# Soundtrap_IMU_board_v4_RXTX_switch.net
KiCad netlist of a schematic drawn in EAGLE
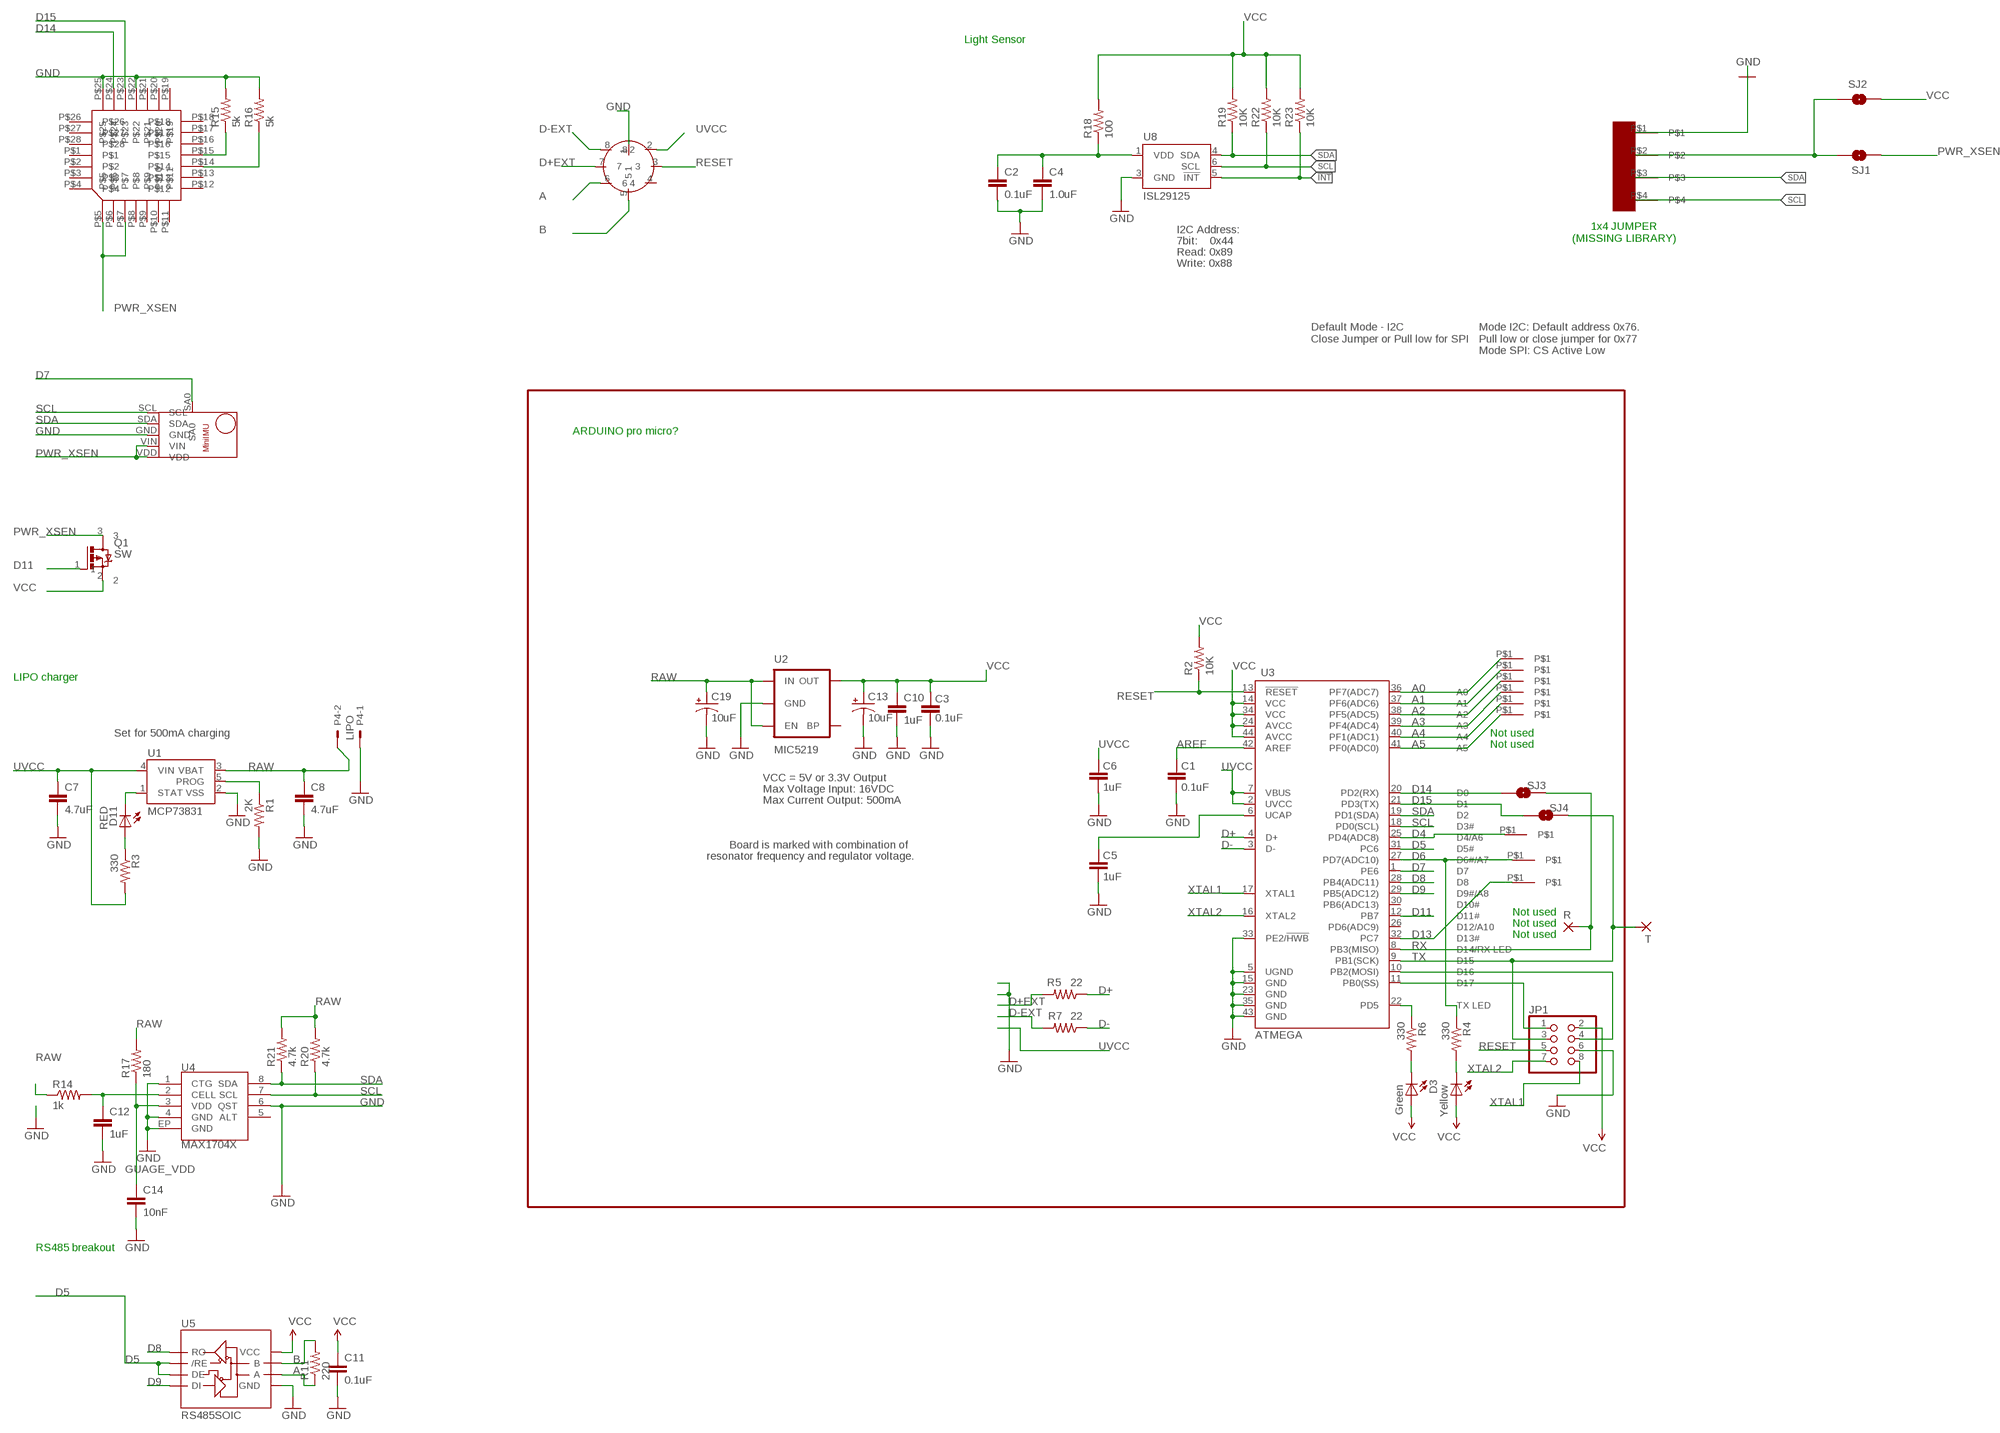
[diagram p0: schematic, sheet 1]

(export (version "E")
  (design (tool "Eeschema 10.0.6"))
  (components
    (comp (ref "C1")
      (value "0.1uF")
      (footprint "eagle-import:0603-CAP")
      (libsource (lib "eagle-import") (part "CAP0603-CAP"))
    )
    (comp (ref "C2")
      (value "0.1uF")
      (footprint "eagle-import:0603-CAP")
      (libsource (lib "eagle-import") (part "0.1UF-25V(+80/-20%)(0603)"))
    )
    (comp (ref "C3")
      (value "0.1uF")
      (footprint "eagle-import:0603-CAP")
      (libsource (lib "eagle-import") (part "CAP0603-CAP"))
    )
    (comp (ref "C4")
      (value "1.0uF")
      (footprint "eagle-import:0603-CAP")
      (libsource (lib "eagle-import") (part "1.0UF-16V-10%(0603)"))
    )
    (comp (ref "C5")
      (value "1uF")
      (footprint "eagle-import:0603-CAP")
      (libsource (lib "eagle-import") (part "CAP0603-CAP"))
    )
    (comp (ref "C6")
      (value "1uF")
      (footprint "eagle-import:0603-CAP")
      (libsource (lib "eagle-import") (part "CAP0603-CAP"))
    )
    (comp (ref "C7")
      (value "4.7uF")
      (footprint "eagle-import:0402-CAP")
      (libsource (lib "eagle-import") (part "CAP0402-CAP"))
    )
    (comp (ref "C8")
      (value "4.7uF")
      (footprint "eagle-import:0402-CAP")
      (libsource (lib "eagle-import") (part "CAP0402-CAP"))
    )
    (comp (ref "C10")
      (value "1uF")
      (footprint "eagle-import:0603-CAP")
      (libsource (lib "eagle-import") (part "CAP0603-CAP"))
    )
    (comp (ref "C11")
      (value "0.1uF")
      (footprint "eagle-import:0402-CAP")
      (libsource (lib "eagle-import") (part "CAP0402-CAP"))
    )
    (comp (ref "C12")
      (value "1uF")
      (footprint "eagle-import:0402-CAP")
      (libsource (lib "eagle-import") (part "CAP0402-CAP"))
    )
    (comp (ref "C13")
      (value "10uF")
      (footprint "eagle-import:EIA3216")
      (libsource (lib "eagle-import") (part "CAP_POL1206"))
    )
    (comp (ref "C14")
      (value "10nF")
      (footprint "eagle-import:0402-CAP")
      (libsource (lib "eagle-import") (part "CAP0402-CAP"))
    )
    (comp (ref "C19")
      (value "10uF")
      (footprint "eagle-import:EIA3216")
      (libsource (lib "eagle-import") (part "CAP_POL1206"))
    )
    (comp (ref "D1")
      (value "Yellow")
      (footprint "eagle-import:LED-0603")
      (libsource (lib "eagle-import") (part "LED0603"))
    )
    (comp (ref "D3")
      (value "Green")
      (footprint "eagle-import:LED-0603")
      (libsource (lib "eagle-import") (part "LED0603"))
    )
    (comp (ref "D11")
      (value "RED")
      (footprint "eagle-import:LED-0603")
      (libsource (lib "eagle-import") (part "LED0603"))
    )
    (comp (ref "JP1")
      (value "PINHD-2X4")
      (footprint "eagle-import:2X04")
      (libsource (lib "eagle-import") (part "PINHD-2X4"))
    )
    (comp (ref "P1")
      (value "SUBCON_MICRO_8_EDGE_ORDERED")
      (footprint "eagle-import:SUBCON_MICRO_8_EDGE")
      (libsource (lib "eagle-import") (part "SUBCON_MICRO_8_EDGE_ORDERED"))
    )
    (comp (ref "P2")
      (value "MINI_IMU")
      (footprint "eagle-import:MINI_IMU")
      (libsource (lib "eagle-import") (part "MINI_IMU"))
    )
    (comp (ref "P3")
      (value "EXT_PRES")
      (footprint "eagle-import:EXT_PRES")
      (libsource (lib "eagle-import") (part "EXT_PRES"))
    )
    (comp (ref "P4")
      (value "LIPO")
      (footprint "eagle-import:22-23-2021")
      (fields (field (name "MF") "MOLEX") (field (name "MPN") "22-23-2021"))
      (libsource (lib "eagle-import") (part "22-23-2021"))
    )
    (comp (ref "Q1")
      (value "SW")
      (footprint "eagle-import:SOT23")
      (libsource (lib "eagle-import") (part "INFINEON_BSS84P"))
    )
    (comp (ref "R")
      (value "1,6/0,9")
      (footprint "eagle-import:1,6_0,9")
      (libsource (lib "eagle-import") (part "1,6/0,9"))
    )
    (comp (ref "R1")
      (value "2K")
      (footprint "eagle-import:0402-RES")
      (libsource (lib "eagle-import") (part "RESISTOR0402-RES"))
    )
    (comp (ref "R2")
      (value "10K")
      (footprint "eagle-import:0603-RES")
      (libsource (lib "eagle-import") (part "RESISTOR0603-RES"))
    )
    (comp (ref "R3")
      (value "330")
      (footprint "eagle-import:0402-RES")
      (libsource (lib "eagle-import") (part "RESISTOR0402-RES"))
    )
    (comp (ref "R4")
      (value "330")
      (footprint "eagle-import:0603-RES")
      (libsource (lib "eagle-import") (part "RESISTOR0603-RES"))
    )
    (comp (ref "R5")
      (value "22")
      (footprint "eagle-import:0603-RES")
      (libsource (lib "eagle-import") (part "RESISTOR0603-RES"))
    )
    (comp (ref "R6")
      (value "330")
      (footprint "eagle-import:0603-RES")
      (libsource (lib "eagle-import") (part "RESISTOR0603-RES"))
    )
    (comp (ref "R7")
      (value "22")
      (footprint "eagle-import:0603-RES")
      (libsource (lib "eagle-import") (part "RESISTOR0603-RES"))
    )
    (comp (ref "R11")
      (value "220")
      (footprint "eagle-import:0402-RES")
      (libsource (lib "eagle-import") (part "RESISTOR0402-RES"))
    )
    (comp (ref "R14")
      (value "1k")
      (footprint "eagle-import:0402-RES")
      (libsource (lib "eagle-import") (part "RESISTOR0402-RES"))
    )
    (comp (ref "R15")
      (value "5k")
      (footprint "eagle-import:R0603")
      (libsource (lib "eagle-import") (part "R-US_R0603"))
    )
    (comp (ref "R16")
      (value "5k")
      (footprint "eagle-import:R0603")
      (libsource (lib "eagle-import") (part "R-US_R0603"))
    )
    (comp (ref "R17")
      (value "180")
      (footprint "eagle-import:0402-RES")
      (libsource (lib "eagle-import") (part "RESISTOR0402-RES"))
    )
    (comp (ref "R18")
      (value "100")
      (footprint "eagle-import:0603-RES")
      (libsource (lib "eagle-import") (part "100OHM1/10W1%(0603)"))
    )
    (comp (ref "R19")
      (value "10K")
      (footprint "eagle-import:0603-RES")
      (libsource (lib "eagle-import") (part "10KOHM1/10W1%(0603)0603"))
    )
    (comp (ref "R20")
      (value "4.7k")
      (footprint "eagle-import:0402-RES")
      (libsource (lib "eagle-import") (part "RESISTOR0402-RES"))
    )
    (comp (ref "R21")
      (value "4.7k")
      (footprint "eagle-import:0402-RES")
      (libsource (lib "eagle-import") (part "RESISTOR0402-RES"))
    )
    (comp (ref "R22")
      (value "10K")
      (footprint "eagle-import:0603-RES")
      (libsource (lib "eagle-import") (part "10KOHM1/10W1%(0603)0603"))
    )
    (comp (ref "R23")
      (value "10K")
      (footprint "eagle-import:0603-RES")
      (libsource (lib "eagle-import") (part "10KOHM1/10W1%(0603)0603"))
    )
    (comp (ref "SJ1")
      (value "SJ1")
      (footprint "eagle-import:SJ_2S-NO")
      (libsource (lib "eagle-import") (part "SOLDERJUMPERNO"))
    )
    (comp (ref "SJ2")
      (value "3v3")
      (footprint "eagle-import:SJ_2S-NO")
      (libsource (lib "eagle-import") (part "SOLDERJUMPERNO"))
    )
    (comp (ref "SJ3")
      (value "SJ1")
      (footprint "eagle-import:SJ_2S-NO")
      (libsource (lib "eagle-import") (part "SOLDERJUMPERNO"))
    )
    (comp (ref "SJ4")
      (value "SJ1")
      (footprint "eagle-import:SJ_2S-NO")
      (libsource (lib "eagle-import") (part "SOLDERJUMPERNO"))
    )
    (comp (ref "T")
      (value "1,6/0,9")
      (footprint "eagle-import:1,6_0,9")
      (libsource (lib "eagle-import") (part "1,6/0,9"))
    )
    (comp (ref "U$5")
      (value "D4")
      (footprint "eagle-import:TEST_POINT")
      (libsource (lib "eagle-import") (part "TEST_POINT"))
    )
    (comp (ref "U$6")
      (value "TEST_POINT")
      (footprint "eagle-import:TEST_POINT")
      (libsource (lib "eagle-import") (part "TEST_POINT"))
    )
    (comp (ref "U$7")
      (value "TEST_POINT")
      (footprint "eagle-import:TEST_POINT")
      (libsource (lib "eagle-import") (part "TEST_POINT"))
    )
    (comp (ref "U$8")
      (value "TEST_POINT")
      (footprint "eagle-import:TEST_POINT")
      (libsource (lib "eagle-import") (part "TEST_POINT"))
    )
    (comp (ref "U$9")
      (value "TEST_POINT")
      (footprint "eagle-import:TEST_POINT")
      (libsource (lib "eagle-import") (part "TEST_POINT"))
    )
    (comp (ref "U$10")
      (value "TEST_POINT")
      (footprint "eagle-import:TEST_POINT")
      (libsource (lib "eagle-import") (part "TEST_POINT"))
    )
    (comp (ref "U$11")
      (value "TEST_POINT")
      (footprint "eagle-import:TEST_POINT")
      (libsource (lib "eagle-import") (part "TEST_POINT"))
    )
    (comp (ref "U$12")
      (value "TEST_POINT")
      (footprint "eagle-import:TEST_POINT")
      (libsource (lib "eagle-import") (part "TEST_POINT"))
    )
    (comp (ref "U$13")
      (value "TEST_POINT")
      (footprint "eagle-import:TEST_POINT")
      (libsource (lib "eagle-import") (part "TEST_POINT"))
    )
    (comp (ref "U1")
      (value "MCP73831")
      (footprint "eagle-import:SOT23-5")
      (libsource (lib "eagle-import") (part "MCP73831"))
    )
    (comp (ref "U2")
      (value "MIC5219")
      (footprint "eagle-import:SOT23-5")
      (libsource (lib "eagle-import") (part "V_REG_LDOSMD"))
    )
    (comp (ref "U3")
      (value "ATMEGA")
      (footprint "eagle-import:QFN-44-NOPAD_1_1-OUTFAKES")
      (libsource (lib "eagle-import") (part "ATMEGA32U4OUTFAKES"))
    )
    (comp (ref "U4")
      (value "MAX1704X")
      (footprint "eagle-import:TDFN-8")
      (libsource (lib "eagle-import") (part "MAX1704X"))
    )
    (comp (ref "U5")
      (value "RS485SOIC")
      (footprint "eagle-import:SO08")
      (libsource (lib "eagle-import") (part "RS485SOIC"))
    )
    (comp (ref "U7")
      (value "XSENSE")
      (footprint "eagle-import:MC-28PLCC-SMT")
      (libsource (lib "eagle-import") (part "XSENSE"))
    )
    (comp (ref "U8")
      (value "ISL29125")
      (footprint "eagle-import:ODFN-LD-6")
      (libsource (lib "eagle-import") (part "ISL29125"))
    )
  )
  (nets
    (net (code "1") (name "/A") (class "Default")
      (node (ref "P1") (pin "6") (pinfunction "6_6") (pintype "bidirectional"))
      (node (ref "R11") (pin "1") (pinfunction "1_1") (pintype "passive"))
      (node (ref "U5") (pin "6") (pinfunction "A_6") (pintype "bidirectional"))
    )
    (net (code "2") (name "/A0") (class "Default")
      (node (ref "U$8") (pin "P$1") (pinfunction "P$1_P$1") (pintype "bidirectional"))
      (node (ref "U3") (pin "36") (pinfunction "PF7(ADC7)_36") (pintype "bidirectional"))
    )
    (net (code "3") (name "/A1") (class "Default")
      (node (ref "U$9") (pin "P$1") (pinfunction "P$1_P$1") (pintype "bidirectional"))
      (node (ref "U3") (pin "37") (pinfunction "PF6(ADC6)_37") (pintype "bidirectional"))
    )
    (net (code "4") (name "/A2") (class "Default")
      (node (ref "U$10") (pin "P$1") (pinfunction "P$1_P$1") (pintype "bidirectional"))
      (node (ref "U3") (pin "38") (pinfunction "PF5(ADC5)_38") (pintype "bidirectional"))
    )
    (net (code "5") (name "/A3") (class "Default")
      (node (ref "U$11") (pin "P$1") (pinfunction "P$1_P$1") (pintype "bidirectional"))
      (node (ref "U3") (pin "39") (pinfunction "PF4(ADC4)_39") (pintype "bidirectional"))
    )
    (net (code "6") (name "/A4") (class "Default")
      (node (ref "U$12") (pin "P$1") (pinfunction "P$1_P$1") (pintype "bidirectional"))
      (node (ref "U3") (pin "40") (pinfunction "PF1(ADC1)_40") (pintype "bidirectional"))
    )
    (net (code "7") (name "/A5") (class "Default")
      (node (ref "U$13") (pin "P$1") (pinfunction "P$1_P$1") (pintype "bidirectional"))
      (node (ref "U3") (pin "41") (pinfunction "PF0(ADC0)_41") (pintype "bidirectional"))
    )
    (net (code "8") (name "/AREF") (class "Default")
      (node (ref "C1") (pin "2") (pinfunction "2_2") (pintype "passive"))
      (node (ref "U3") (pin "42") (pinfunction "AREF_42") (pintype "bidirectional"))
    )
    (net (code "9") (name "/B") (class "Default")
      (node (ref "P1") (pin "5") (pinfunction "5_5") (pintype "bidirectional"))
      (node (ref "R11") (pin "2") (pinfunction "2_2") (pintype "passive"))
      (node (ref "U5") (pin "7") (pinfunction "B_7") (pintype "bidirectional"))
    )
    (net (code "10") (name "/D+") (class "Default")
      (node (ref "R5") (pin "1") (pinfunction "1_1") (pintype "passive"))
      (node (ref "U3") (pin "4") (pinfunction "D+_4") (pintype "bidirectional"))
    )
    (net (code "11") (name "/D+EXT") (class "Default")
      (node (ref "P1") (pin "7") (pinfunction "7_7") (pintype "bidirectional"))
      (node (ref "R5") (pin "2") (pinfunction "2_2") (pintype "passive"))
    )
    (net (code "12") (name "/D-") (class "Default")
      (node (ref "R7") (pin "1") (pinfunction "1_1") (pintype "passive"))
      (node (ref "U3") (pin "3") (pinfunction "D-_3") (pintype "bidirectional"))
    )
    (net (code "13") (name "/D-EXT") (class "Default")
      (node (ref "P1") (pin "8") (pinfunction "8_8") (pintype "bidirectional"))
      (node (ref "R7") (pin "2") (pinfunction "2_2") (pintype "passive"))
    )
    (net (code "14") (name "/D4") (class "Default")
      (node (ref "U$5") (pin "P$1") (pinfunction "P$1_P$1") (pintype "bidirectional"))
      (node (ref "U3") (pin "25") (pinfunction "PD4(ADC8)_25") (pintype "bidirectional"))
    )
    (net (code "15") (name "/D5") (class "Default")
      (node (ref "U3") (pin "31") (pinfunction "PC6_31") (pintype "bidirectional"))
      (node (ref "U5") (pin "2") (pinfunction "/RE_2") (pintype "bidirectional"))
      (node (ref "U5") (pin "3") (pinfunction "DE_3") (pintype "bidirectional"))
    )
    (net (code "16") (name "/D6") (class "Default")
      (node (ref "R4") (pin "1") (pinfunction "1_1") (pintype "passive"))
      (node (ref "U$6") (pin "P$1") (pinfunction "P$1_P$1") (pintype "bidirectional"))
      (node (ref "U3") (pin "27") (pinfunction "PD7(ADC10)_27") (pintype "bidirectional"))
    )
    (net (code "17") (name "/D7") (class "Default")
      (node (ref "P2") (pin "SA0") (pinfunction "SA0_SA0") (pintype "bidirectional"))
      (node (ref "U3") (pin "1") (pinfunction "PE6_1") (pintype "bidirectional"))
    )
    (net (code "18") (name "/D8") (class "Default")
      (node (ref "U3") (pin "28") (pinfunction "PB4(ADC11)_28") (pintype "bidirectional"))
      (node (ref "U5") (pin "1") (pinfunction "RO_1") (pintype "bidirectional"))
    )
    (net (code "19") (name "/D9") (class "Default")
      (node (ref "U3") (pin "29") (pinfunction "PB5(ADC12)_29") (pintype "bidirectional"))
      (node (ref "U5") (pin "4") (pinfunction "DI_4") (pintype "bidirectional"))
    )
    (net (code "20") (name "/D11") (class "Default")
      (node (ref "Q1") (pin "1") (pinfunction "1_1") (pintype "input"))
      (node (ref "U3") (pin "12") (pinfunction "PB7_12") (pintype "bidirectional"))
    )
    (net (code "21") (name "/D13") (class "Default")
      (node (ref "U$7") (pin "P$1") (pinfunction "P$1_P$1") (pintype "bidirectional"))
      (node (ref "U3") (pin "32") (pinfunction "PC7_32") (pintype "bidirectional"))
    )
    (net (code "22") (name "/D14") (class "Default")
      (node (ref "SJ3") (pin "2") (pinfunction "2_2") (pintype "passive"))
      (node (ref "U3") (pin "20") (pinfunction "PD2(RX)_20") (pintype "bidirectional"))
      (node (ref "U7") (pin "P$24") (pinfunction "P$24_P$24") (pintype "bidirectional"))
    )
    (net (code "23") (name "/D15") (class "Default")
      (node (ref "SJ4") (pin "2") (pinfunction "2_2") (pintype "passive"))
      (node (ref "U3") (pin "21") (pinfunction "PD3(TX)_21") (pintype "bidirectional"))
      (node (ref "U7") (pin "P$23") (pinfunction "P$23_P$23") (pintype "bidirectional"))
    )
    (net (code "24") (name "/GUAGE_VDD") (class "Default")
      (node (ref "C14") (pin "1") (pinfunction "1_1") (pintype "passive"))
      (node (ref "R17") (pin "1") (pinfunction "1_1") (pintype "passive"))
      (node (ref "U4") (pin "3") (pinfunction "VDD_3") (pintype "bidirectional"))
    )
    (net (code "25") (name "/PWR_XSEN") (class "Default")
      (node (ref "P2") (pin "VDD") (pinfunction "VDD_VDD") (pintype "power_in"))
      (node (ref "P2") (pin "VIN") (pinfunction "VIN_VIN") (pintype "power_in"))
      (node (ref "Q1") (pin "3") (pinfunction "3_3") (pintype "output"))
      (node (ref "SJ1") (pin "1") (pinfunction "1_1") (pintype "passive"))
      (node (ref "U7") (pin "P$5") (pinfunction "P$5_P$5") (pintype "bidirectional"))
      (node (ref "U7") (pin "P$7") (pinfunction "P$7_P$7") (pintype "bidirectional"))
    )
    (net (code "26") (name "/RAW") (class "Default")
      (node (ref "C19") (pin "A") (pinfunction "+_A") (pintype "passive"))
      (node (ref "C8") (pin "1") (pinfunction "1_1") (pintype "passive"))
      (node (ref "P4") (pin "2") (pinfunction "S_2") (pintype "passive"))
      (node (ref "R14") (pin "1") (pinfunction "1_1") (pintype "passive"))
      (node (ref "R17") (pin "2") (pinfunction "2_2") (pintype "passive"))
      (node (ref "R20") (pin "2") (pinfunction "2_2") (pintype "passive"))
      (node (ref "R21") (pin "2") (pinfunction "2_2") (pintype "passive"))
      (node (ref "U1") (pin "3") (pinfunction "VBAT_3") (pintype "power_in"))
      (node (ref "U2") (pin "1") (pinfunction "IN_1") (pintype "input"))
      (node (ref "U2") (pin "3") (pinfunction "EN_3") (pintype "input"))
    )
    (net (code "27") (name "/RESET") (class "Default")
      (node (ref "JP1") (pin "5") (pinfunction "5_5") (pintype "passive"))
      (node (ref "P1") (pin "3") (pinfunction "3_3") (pintype "bidirectional"))
      (node (ref "R2") (pin "1") (pinfunction "1_1") (pintype "passive"))
      (node (ref "U3") (pin "13") (pinfunction "~{RESET}_13") (pintype "bidirectional"))
    )
    (net (code "28") (name "/RX") (class "Default")
      (node (ref "R") (pin "1") (pinfunction "P_1") (pintype "passive"))
      (node (ref "SJ3") (pin "1") (pinfunction "1_1") (pintype "passive"))
      (node (ref "U3") (pin "8") (pinfunction "PB3(MISO)_8") (pintype "bidirectional"))
    )
    (net (code "29") (name "/TX") (class "Default")
      (node (ref "JP1") (pin "3") (pinfunction "3_3") (pintype "passive"))
      (node (ref "SJ4") (pin "1") (pinfunction "1_1") (pintype "passive"))
      (node (ref "T") (pin "1") (pinfunction "P_1") (pintype "passive"))
      (node (ref "U3") (pin "9") (pinfunction "PB1(SCK)_9") (pintype "bidirectional"))
    )
    (net (code "30") (name "/UVCC") (class "Default")
      (node (ref "C6") (pin "2") (pinfunction "2_2") (pintype "passive"))
      (node (ref "C7") (pin "1") (pinfunction "1_1") (pintype "passive"))
      (node (ref "P1") (pin "2") (pinfunction "2_2") (pintype "bidirectional"))
      (node (ref "R3") (pin "2") (pinfunction "2_2") (pintype "passive"))
      (node (ref "U1") (pin "4") (pinfunction "VIN_4") (pintype "power_in"))
      (node (ref "U3") (pin "2") (pinfunction "UVCC_2") (pintype "bidirectional"))
      (node (ref "U3") (pin "7") (pinfunction "VBUS_7") (pintype "bidirectional"))
    )
    (net (code "31") (name "/XTAL1") (class "Default")
      (node (ref "JP1") (pin "8") (pinfunction "8_8") (pintype "passive"))
      (node (ref "U3") (pin "17") (pinfunction "XTAL1_17") (pintype "bidirectional"))
    )
    (net (code "32") (name "/XTAL2") (class "Default")
      (node (ref "JP1") (pin "7") (pinfunction "7_7") (pintype "passive"))
      (node (ref "U3") (pin "16") (pinfunction "XTAL2_16") (pintype "bidirectional"))
    )
    (net (code "33") (name "/~{INT}") (class "Default")
      (node (ref "R23") (pin "1") (pinfunction "1_1") (pintype "passive"))
      (node (ref "U8") (pin "5") (pinfunction "~{INT}_5") (pintype "bidirectional"))
    )
    (net (code "34") (name "GND") (class "Default")
      (node (ref "C1") (pin "1") (pinfunction "1_1") (pintype "passive"))
      (node (ref "C10") (pin "2") (pinfunction "2_2") (pintype "passive"))
      (node (ref "C11") (pin "2") (pinfunction "2_2") (pintype "passive"))
      (node (ref "C12") (pin "2") (pinfunction "2_2") (pintype "passive"))
      (node (ref "C13") (pin "C") (pinfunction "-_C") (pintype "passive"))
      (node (ref "C14") (pin "2") (pinfunction "2_2") (pintype "passive"))
      (node (ref "C19") (pin "C") (pinfunction "-_C") (pintype "passive"))
      (node (ref "C2") (pin "2") (pinfunction "2_2") (pintype "passive"))
      (node (ref "C3") (pin "1") (pinfunction "1_1") (pintype "passive"))
      (node (ref "C4") (pin "2") (pinfunction "2_2") (pintype "passive"))
      (node (ref "C5") (pin "1") (pinfunction "1_1") (pintype "passive"))
      (node (ref "C6") (pin "1") (pinfunction "1_1") (pintype "passive"))
      (node (ref "C7") (pin "2") (pinfunction "2_2") (pintype "passive"))
      (node (ref "C8") (pin "2") (pinfunction "2_2") (pintype "passive"))
      (node (ref "JP1") (pin "6") (pinfunction "6_6") (pintype "passive"))
      (node (ref "P1") (pin "1") (pinfunction "1_1") (pintype "bidirectional"))
      (node (ref "P2") (pin "GND") (pinfunction "GND_GND") (pintype "bidirectional"))
      (node (ref "P3") (pin "P$1") (pinfunction "P$1_P$1") (pintype "bidirectional"))
      (node (ref "P4") (pin "1") (pinfunction "S_1") (pintype "passive"))
      (node (ref "R1") (pin "2") (pinfunction "2_2") (pintype "passive"))
      (node (ref "R15") (pin "2") (pinfunction "2_2") (pintype "passive"))
      (node (ref "R16") (pin "2") (pinfunction "2_2") (pintype "passive"))
      (node (ref "U1") (pin "2") (pinfunction "VSS_2") (pintype "power_in"))
      (node (ref "U2") (pin "2") (pinfunction "GND_2") (pintype "input"))
      (node (ref "U3") (pin "15") (pinfunction "GND_15") (pintype "bidirectional"))
      (node (ref "U3") (pin "23") (pinfunction "GND_23") (pintype "bidirectional"))
      (node (ref "U3") (pin "33") (pinfunction "PE2/~{HWB}_33") (pintype "bidirectional"))
      (node (ref "U3") (pin "35") (pinfunction "GND_35") (pintype "bidirectional"))
      (node (ref "U3") (pin "43") (pinfunction "GND_43") (pintype "bidirectional"))
      (node (ref "U3") (pin "5") (pinfunction "UGND_5") (pintype "bidirectional"))
      (node (ref "U4") (pin "1") (pinfunction "CTG_1") (pintype "bidirectional"))
      (node (ref "U4") (pin "4") (pinfunction "GND_4") (pintype "bidirectional"))
      (node (ref "U4") (pin "6") (pinfunction "QST_6") (pintype "bidirectional"))
      (node (ref "U4") (pin "EP") (pinfunction "GND_EP") (pintype "bidirectional"))
      (node (ref "U5") (pin "5") (pinfunction "GND_5") (pintype "bidirectional"))
      (node (ref "U7") (pin "P$22") (pinfunction "P$22_P$22") (pintype "bidirectional"))
      (node (ref "U7") (pin "P$25") (pinfunction "P$25_P$25") (pintype "bidirectional"))
      (node (ref "U8") (pin "3") (pinfunction "GND_3") (pintype "bidirectional"))
    )
    (net (code "35") (name "Net-(D1-PadC)") (class "Default")
      (node (ref "D1") (pin "C") (pinfunction "C_C") (pintype "passive"))
      (node (ref "R4") (pin "2") (pinfunction "2_2") (pintype "passive"))
    )
    (net (code "36") (name "Net-(D3-PadC)") (class "Default")
      (node (ref "D3") (pin "C") (pinfunction "C_C") (pintype "passive"))
      (node (ref "R6") (pin "2") (pinfunction "2_2") (pintype "passive"))
    )
    (net (code "37") (name "Net-(D11-PadA)") (class "Default")
      (node (ref "D11") (pin "A") (pinfunction "A_A") (pintype "passive"))
      (node (ref "R3") (pin "1") (pinfunction "1_1") (pintype "passive"))
    )
    (net (code "38") (name "Net-(P3-PadP$2)") (class "Default")
      (node (ref "P3") (pin "P$2") (pinfunction "P$2_P$2") (pintype "bidirectional"))
      (node (ref "SJ1") (pin "2") (pinfunction "2_2") (pintype "passive"))
      (node (ref "SJ2") (pin "1") (pinfunction "1_1") (pintype "passive"))
    )
    (net (code "39") (name "Net-(R15-Pad1)") (class "Default")
      (node (ref "R15") (pin "1") (pinfunction "1_1") (pintype "passive"))
      (node (ref "U7") (pin "P$15") (pinfunction "P$15_P$15") (pintype "bidirectional"))
    )
    (net (code "40") (name "Net-(R16-Pad1)") (class "Default")
      (node (ref "R16") (pin "1") (pinfunction "1_1") (pintype "passive"))
      (node (ref "U7") (pin "P$14") (pinfunction "P$14_P$14") (pintype "bidirectional"))
    )
    (net (code "41") (name "Net-(U1-PROG)") (class "Default")
      (node (ref "R1") (pin "1") (pinfunction "1_1") (pintype "passive"))
      (node (ref "U1") (pin "5") (pinfunction "PROG_5") (pintype "input"))
    )
    (net (code "42") (name "Net-(U1-STAT)") (class "Default")
      (node (ref "D11") (pin "C") (pinfunction "C_C") (pintype "passive"))
      (node (ref "U1") (pin "1") (pinfunction "STAT_1") (pintype "output"))
    )
    (net (code "43") (name "Net-(U3-PB0(SS))") (class "Default")
      (node (ref "JP1") (pin "1") (pinfunction "1_1") (pintype "passive"))
      (node (ref "U3") (pin "11") (pinfunction "PB0(SS)_11") (pintype "bidirectional"))
    )
    (net (code "44") (name "Net-(U3-PB2(MOSI))") (class "Default")
      (node (ref "JP1") (pin "4") (pinfunction "4_4") (pintype "passive"))
      (node (ref "U3") (pin "10") (pinfunction "PB2(MOSI)_10") (pintype "bidirectional"))
    )
    (net (code "45") (name "Net-(U3-PD5)") (class "Default")
      (node (ref "R6") (pin "1") (pinfunction "1_1") (pintype "passive"))
      (node (ref "U3") (pin "22") (pinfunction "PD5_22") (pintype "bidirectional"))
    )
    (net (code "46") (name "Net-(U3-UCAP)") (class "Default")
      (node (ref "C5") (pin "2") (pinfunction "2_2") (pintype "passive"))
      (node (ref "U3") (pin "6") (pinfunction "UCAP_6") (pintype "bidirectional"))
    )
    (net (code "47") (name "Net-(U4-CELL)") (class "Default")
      (node (ref "C12") (pin "1") (pinfunction "1_1") (pintype "passive"))
      (node (ref "R14") (pin "2") (pinfunction "2_2") (pintype "passive"))
      (node (ref "U4") (pin "2") (pinfunction "CELL_2") (pintype "bidirectional"))
    )
    (net (code "48") (name "Net-(U8-VDD)") (class "Default")
      (node (ref "C2") (pin "1") (pinfunction "1_1") (pintype "passive"))
      (node (ref "C4") (pin "1") (pinfunction "1_1") (pintype "passive"))
      (node (ref "R18") (pin "1") (pinfunction "1_1") (pintype "passive"))
      (node (ref "U8") (pin "1") (pinfunction "VDD_1") (pintype "bidirectional"))
    )
    (net (code "49") (name "SCL") (class "Default")
      (node (ref "P2") (pin "SCL") (pinfunction "SCL_SCL") (pintype "bidirectional"))
      (node (ref "P3") (pin "P$4") (pinfunction "P$4_P$4") (pintype "bidirectional"))
      (node (ref "R20") (pin "1") (pinfunction "1_1") (pintype "passive"))
      (node (ref "R22") (pin "1") (pinfunction "1_1") (pintype "passive"))
      (node (ref "U3") (pin "18") (pinfunction "PD0(SCL)_18") (pintype "bidirectional"))
      (node (ref "U4") (pin "7") (pinfunction "SCL_7") (pintype "bidirectional"))
      (node (ref "U8") (pin "6") (pinfunction "SCL_6") (pintype "bidirectional"))
    )
    (net (code "50") (name "SDA") (class "Default")
      (node (ref "P2") (pin "SDA") (pinfunction "SDA_SDA") (pintype "bidirectional"))
      (node (ref "P3") (pin "P$3") (pinfunction "P$3_P$3") (pintype "bidirectional"))
      (node (ref "R19") (pin "1") (pinfunction "1_1") (pintype "passive"))
      (node (ref "R21") (pin "1") (pinfunction "1_1") (pintype "passive"))
      (node (ref "U3") (pin "19") (pinfunction "PD1(SDA)_19") (pintype "bidirectional"))
      (node (ref "U4") (pin "8") (pinfunction "SDA_8") (pintype "bidirectional"))
      (node (ref "U8") (pin "4") (pinfunction "SDA_4") (pintype "bidirectional"))
    )
    (net (code "51") (name "VCC") (class "Default")
      (node (ref "C10") (pin "1") (pinfunction "1_1") (pintype "passive"))
      (node (ref "C11") (pin "1") (pinfunction "1_1") (pintype "passive"))
      (node (ref "C13") (pin "A") (pinfunction "+_A") (pintype "passive"))
      (node (ref "C3") (pin "2") (pinfunction "2_2") (pintype "passive"))
      (node (ref "D1") (pin "A") (pinfunction "A_A") (pintype "passive"))
      (node (ref "D3") (pin "A") (pinfunction "A_A") (pintype "passive"))
      (node (ref "JP1") (pin "2") (pinfunction "2_2") (pintype "passive"))
      (node (ref "Q1") (pin "2") (pinfunction "2_2") (pintype "input"))
      (node (ref "R18") (pin "2") (pinfunction "2_2") (pintype "passive"))
      (node (ref "R19") (pin "2") (pinfunction "2_2") (pintype "passive"))
      (node (ref "R2") (pin "2") (pinfunction "2_2") (pintype "passive"))
      (node (ref "R22") (pin "2") (pinfunction "2_2") (pintype "passive"))
      (node (ref "R23") (pin "2") (pinfunction "2_2") (pintype "passive"))
      (node (ref "SJ2") (pin "2") (pinfunction "2_2") (pintype "passive"))
      (node (ref "U2") (pin "5") (pinfunction "OUT_5") (pintype "passive"))
      (node (ref "U3") (pin "14") (pinfunction "VCC_14") (pintype "bidirectional"))
      (node (ref "U3") (pin "24") (pinfunction "AVCC_24") (pintype "bidirectional"))
      (node (ref "U3") (pin "34") (pinfunction "VCC_34") (pintype "bidirectional"))
      (node (ref "U3") (pin "44") (pinfunction "AVCC_44") (pintype "bidirectional"))
      (node (ref "U5") (pin "8") (pinfunction "VCC_8") (pintype "bidirectional"))
    )
    (net (code "52") (name "unconnected-(P1-Pad4)") (class "Default")
      (node (ref "P1") (pin "4") (pinfunction "4_4") (pintype "bidirectional"))
    )
    (net (code "53") (name "unconnected-(U2-BP-Pad4)") (class "Default")
      (node (ref "U2") (pin "4") (pinfunction "BP_4") (pintype "input"))
    )
    (net (code "54") (name "unconnected-(U3-PB6(ADC13)-Pad30)") (class "Default")
      (node (ref "U3") (pin "30") (pinfunction "PB6(ADC13)_30") (pintype "bidirectional"))
    )
    (net (code "55") (name "unconnected-(U3-PD6(ADC9)-Pad26)") (class "Default")
      (node (ref "U3") (pin "26") (pinfunction "PD6(ADC9)_26") (pintype "bidirectional"))
    )
    (net (code "56") (name "unconnected-(U4-ALT-Pad5)") (class "Default")
      (node (ref "U4") (pin "5") (pinfunction "ALT_5") (pintype "bidirectional"))
    )
    (net (code "57") (name "unconnected-(U7-PadP$1)") (class "Default")
      (node (ref "U7") (pin "P$1") (pinfunction "P$1_P$1") (pintype "bidirectional"))
    )
    (net (code "58") (name "unconnected-(U7-PadP$2)") (class "Default")
      (node (ref "U7") (pin "P$2") (pinfunction "P$2_P$2") (pintype "bidirectional"))
    )
    (net (code "59") (name "unconnected-(U7-PadP$3)") (class "Default")
      (node (ref "U7") (pin "P$3") (pinfunction "P$3_P$3") (pintype "bidirectional"))
    )
    (net (code "60") (name "unconnected-(U7-PadP$4)") (class "Default")
      (node (ref "U7") (pin "P$4") (pinfunction "P$4_P$4") (pintype "bidirectional"))
    )
    (net (code "61") (name "unconnected-(U7-PadP$6)") (class "Default")
      (node (ref "U7") (pin "P$6") (pinfunction "P$6_P$6") (pintype "bidirectional"))
    )
    (net (code "62") (name "unconnected-(U7-PadP$8)") (class "Default")
      (node (ref "U7") (pin "P$8") (pinfunction "P$8_P$8") (pintype "bidirectional"))
    )
    (net (code "63") (name "unconnected-(U7-PadP$9)") (class "Default")
      (node (ref "U7") (pin "P$9") (pinfunction "P$9_P$9") (pintype "bidirectional"))
    )
    (net (code "64") (name "unconnected-(U7-PadP$10)") (class "Default")
      (node (ref "U7") (pin "P$10") (pinfunction "P$10_P$10") (pintype "bidirectional"))
    )
    (net (code "65") (name "unconnected-(U7-PadP$11)") (class "Default")
      (node (ref "U7") (pin "P$11") (pinfunction "P$11_P$11") (pintype "bidirectional"))
    )
    (net (code "66") (name "unconnected-(U7-PadP$12)") (class "Default")
      (node (ref "U7") (pin "P$12") (pinfunction "P$12_P$12") (pintype "bidirectional"))
    )
    (net (code "67") (name "unconnected-(U7-PadP$13)") (class "Default")
      (node (ref "U7") (pin "P$13") (pinfunction "P$13_P$13") (pintype "bidirectional"))
    )
    (net (code "68") (name "unconnected-(U7-PadP$16)") (class "Default")
      (node (ref "U7") (pin "P$16") (pinfunction "P$16_P$16") (pintype "bidirectional"))
    )
    (net (code "69") (name "unconnected-(U7-PadP$17)") (class "Default")
      (node (ref "U7") (pin "P$17") (pinfunction "P$17_P$17") (pintype "bidirectional"))
    )
    (net (code "70") (name "unconnected-(U7-PadP$18)") (class "Default")
      (node (ref "U7") (pin "P$18") (pinfunction "P$18_P$18") (pintype "bidirectional"))
    )
    (net (code "71") (name "unconnected-(U7-PadP$19)") (class "Default")
      (node (ref "U7") (pin "P$19") (pinfunction "P$19_P$19") (pintype "bidirectional"))
    )
    (net (code "72") (name "unconnected-(U7-PadP$20)") (class "Default")
      (node (ref "U7") (pin "P$20") (pinfunction "P$20_P$20") (pintype "bidirectional"))
    )
    (net (code "73") (name "unconnected-(U7-PadP$21)") (class "Default")
      (node (ref "U7") (pin "P$21") (pinfunction "P$21_P$21") (pintype "bidirectional"))
    )
    (net (code "74") (name "unconnected-(U7-PadP$26)") (class "Default")
      (node (ref "U7") (pin "P$26") (pinfunction "P$26_P$26") (pintype "bidirectional"))
    )
    (net (code "75") (name "unconnected-(U7-PadP$27)") (class "Default")
      (node (ref "U7") (pin "P$27") (pinfunction "P$27_P$27") (pintype "bidirectional"))
    )
    (net (code "76") (name "unconnected-(U7-PadP$28)") (class "Default")
      (node (ref "U7") (pin "P$28") (pinfunction "P$28_P$28") (pintype "bidirectional"))
    )
  )
)
